# tester.net
KiCad netlist of a schematic drawn in EAGLE
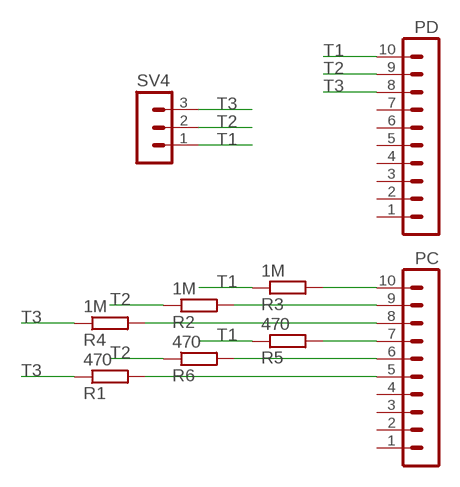
[diagram p0: schematic, sheet 1]

(export (version "E")
  (design (tool "Eeschema 10.0.6"))
  (components
    (comp (ref "PC")
      (value "MA10-1W")
      (footprint "eagle-import:MA10-1W")
      (libsource (lib "eagle-import") (part "MA10-1W"))
    )
    (comp (ref "PD")
      (value "MA10-1W")
      (footprint "eagle-import:MA10-1W")
      (libsource (lib "eagle-import") (part "MA10-1W"))
    )
    (comp (ref "R1")
      (value "470")
      (footprint "eagle-import:R1206")
      (libsource (lib "eagle-import") (part "R-EU_R1206"))
    )
    (comp (ref "R2")
      (value "1M")
      (footprint "eagle-import:R1206")
      (libsource (lib "eagle-import") (part "R-EU_R1206"))
    )
    (comp (ref "R3")
      (value "1M")
      (footprint "eagle-import:R1206")
      (libsource (lib "eagle-import") (part "R-EU_R1206"))
    )
    (comp (ref "R4")
      (value "1M")
      (footprint "eagle-import:R1206")
      (libsource (lib "eagle-import") (part "R-EU_R1206"))
    )
    (comp (ref "R5")
      (value "470")
      (footprint "eagle-import:R1206")
      (libsource (lib "eagle-import") (part "R-EU_R1206"))
    )
    (comp (ref "R6")
      (value "470")
      (footprint "eagle-import:R1206")
      (libsource (lib "eagle-import") (part "R-EU_R1206"))
    )
    (comp (ref "SV4")
      (value "MA03-1")
      (footprint "eagle-import:MA03-1")
      (libsource (lib "eagle-import") (part "MA03-1"))
    )
  )
  (nets
    (net (code "1") (name "/T1") (class "Default")
      (node (ref "PD") (pin "10") (pinfunction "10_10") (pintype "passive"))
      (node (ref "R3") (pin "1") (pinfunction "1_1") (pintype "passive"))
      (node (ref "R5") (pin "1") (pinfunction "1_1") (pintype "passive"))
      (node (ref "SV4") (pin "1") (pinfunction "1_1") (pintype "passive"))
    )
    (net (code "2") (name "/T2") (class "Default")
      (node (ref "PD") (pin "9") (pinfunction "9_9") (pintype "passive"))
      (node (ref "R2") (pin "1") (pinfunction "1_1") (pintype "passive"))
      (node (ref "R6") (pin "1") (pinfunction "1_1") (pintype "passive"))
      (node (ref "SV4") (pin "2") (pinfunction "2_2") (pintype "passive"))
    )
    (net (code "3") (name "/T3") (class "Default")
      (node (ref "PD") (pin "8") (pinfunction "8_8") (pintype "passive"))
      (node (ref "R1") (pin "1") (pinfunction "1_1") (pintype "passive"))
      (node (ref "R4") (pin "1") (pinfunction "1_1") (pintype "passive"))
      (node (ref "SV4") (pin "3") (pinfunction "3_3") (pintype "passive"))
    )
    (net (code "4") (name "Net-(PC-Pad5)") (class "Default")
      (node (ref "PC") (pin "5") (pinfunction "5_5") (pintype "passive"))
      (node (ref "R1") (pin "2") (pinfunction "2_2") (pintype "passive"))
    )
    (net (code "5") (name "Net-(PC-Pad6)") (class "Default")
      (node (ref "PC") (pin "6") (pinfunction "6_6") (pintype "passive"))
      (node (ref "R6") (pin "2") (pinfunction "2_2") (pintype "passive"))
    )
    (net (code "6") (name "Net-(PC-Pad7)") (class "Default")
      (node (ref "PC") (pin "7") (pinfunction "7_7") (pintype "passive"))
      (node (ref "R5") (pin "2") (pinfunction "2_2") (pintype "passive"))
    )
    (net (code "7") (name "Net-(PC-Pad8)") (class "Default")
      (node (ref "PC") (pin "8") (pinfunction "8_8") (pintype "passive"))
      (node (ref "R4") (pin "2") (pinfunction "2_2") (pintype "passive"))
    )
    (net (code "8") (name "Net-(PC-Pad9)") (class "Default")
      (node (ref "PC") (pin "9") (pinfunction "9_9") (pintype "passive"))
      (node (ref "R2") (pin "2") (pinfunction "2_2") (pintype "passive"))
    )
    (net (code "9") (name "Net-(PC-Pad10)") (class "Default")
      (node (ref "PC") (pin "10") (pinfunction "10_10") (pintype "passive"))
      (node (ref "R3") (pin "2") (pinfunction "2_2") (pintype "passive"))
    )
    (net (code "10") (name "unconnected-(PC-Pad1)") (class "Default")
      (node (ref "PC") (pin "1") (pinfunction "1_1") (pintype "passive"))
    )
    (net (code "11") (name "unconnected-(PC-Pad2)") (class "Default")
      (node (ref "PC") (pin "2") (pinfunction "2_2") (pintype "passive"))
    )
    (net (code "12") (name "unconnected-(PC-Pad3)") (class "Default")
      (node (ref "PC") (pin "3") (pinfunction "3_3") (pintype "passive"))
    )
    (net (code "13") (name "unconnected-(PC-Pad4)") (class "Default")
      (node (ref "PC") (pin "4") (pinfunction "4_4") (pintype "passive"))
    )
    (net (code "14") (name "unconnected-(PD-Pad1)") (class "Default")
      (node (ref "PD") (pin "1") (pinfunction "1_1") (pintype "passive"))
    )
    (net (code "15") (name "unconnected-(PD-Pad2)") (class "Default")
      (node (ref "PD") (pin "2") (pinfunction "2_2") (pintype "passive"))
    )
    (net (code "16") (name "unconnected-(PD-Pad3)") (class "Default")
      (node (ref "PD") (pin "3") (pinfunction "3_3") (pintype "passive"))
    )
    (net (code "17") (name "unconnected-(PD-Pad4)") (class "Default")
      (node (ref "PD") (pin "4") (pinfunction "4_4") (pintype "passive"))
    )
    (net (code "18") (name "unconnected-(PD-Pad5)") (class "Default")
      (node (ref "PD") (pin "5") (pinfunction "5_5") (pintype "passive"))
    )
    (net (code "19") (name "unconnected-(PD-Pad6)") (class "Default")
      (node (ref "PD") (pin "6") (pinfunction "6_6") (pintype "passive"))
    )
    (net (code "20") (name "unconnected-(PD-Pad7)") (class "Default")
      (node (ref "PD") (pin "7") (pinfunction "7_7") (pintype "passive"))
    )
  )
)
